# Trig_to_Gate_Converter_ctrl_V1.net
KiCad netlist of a schematic drawn in EAGLE
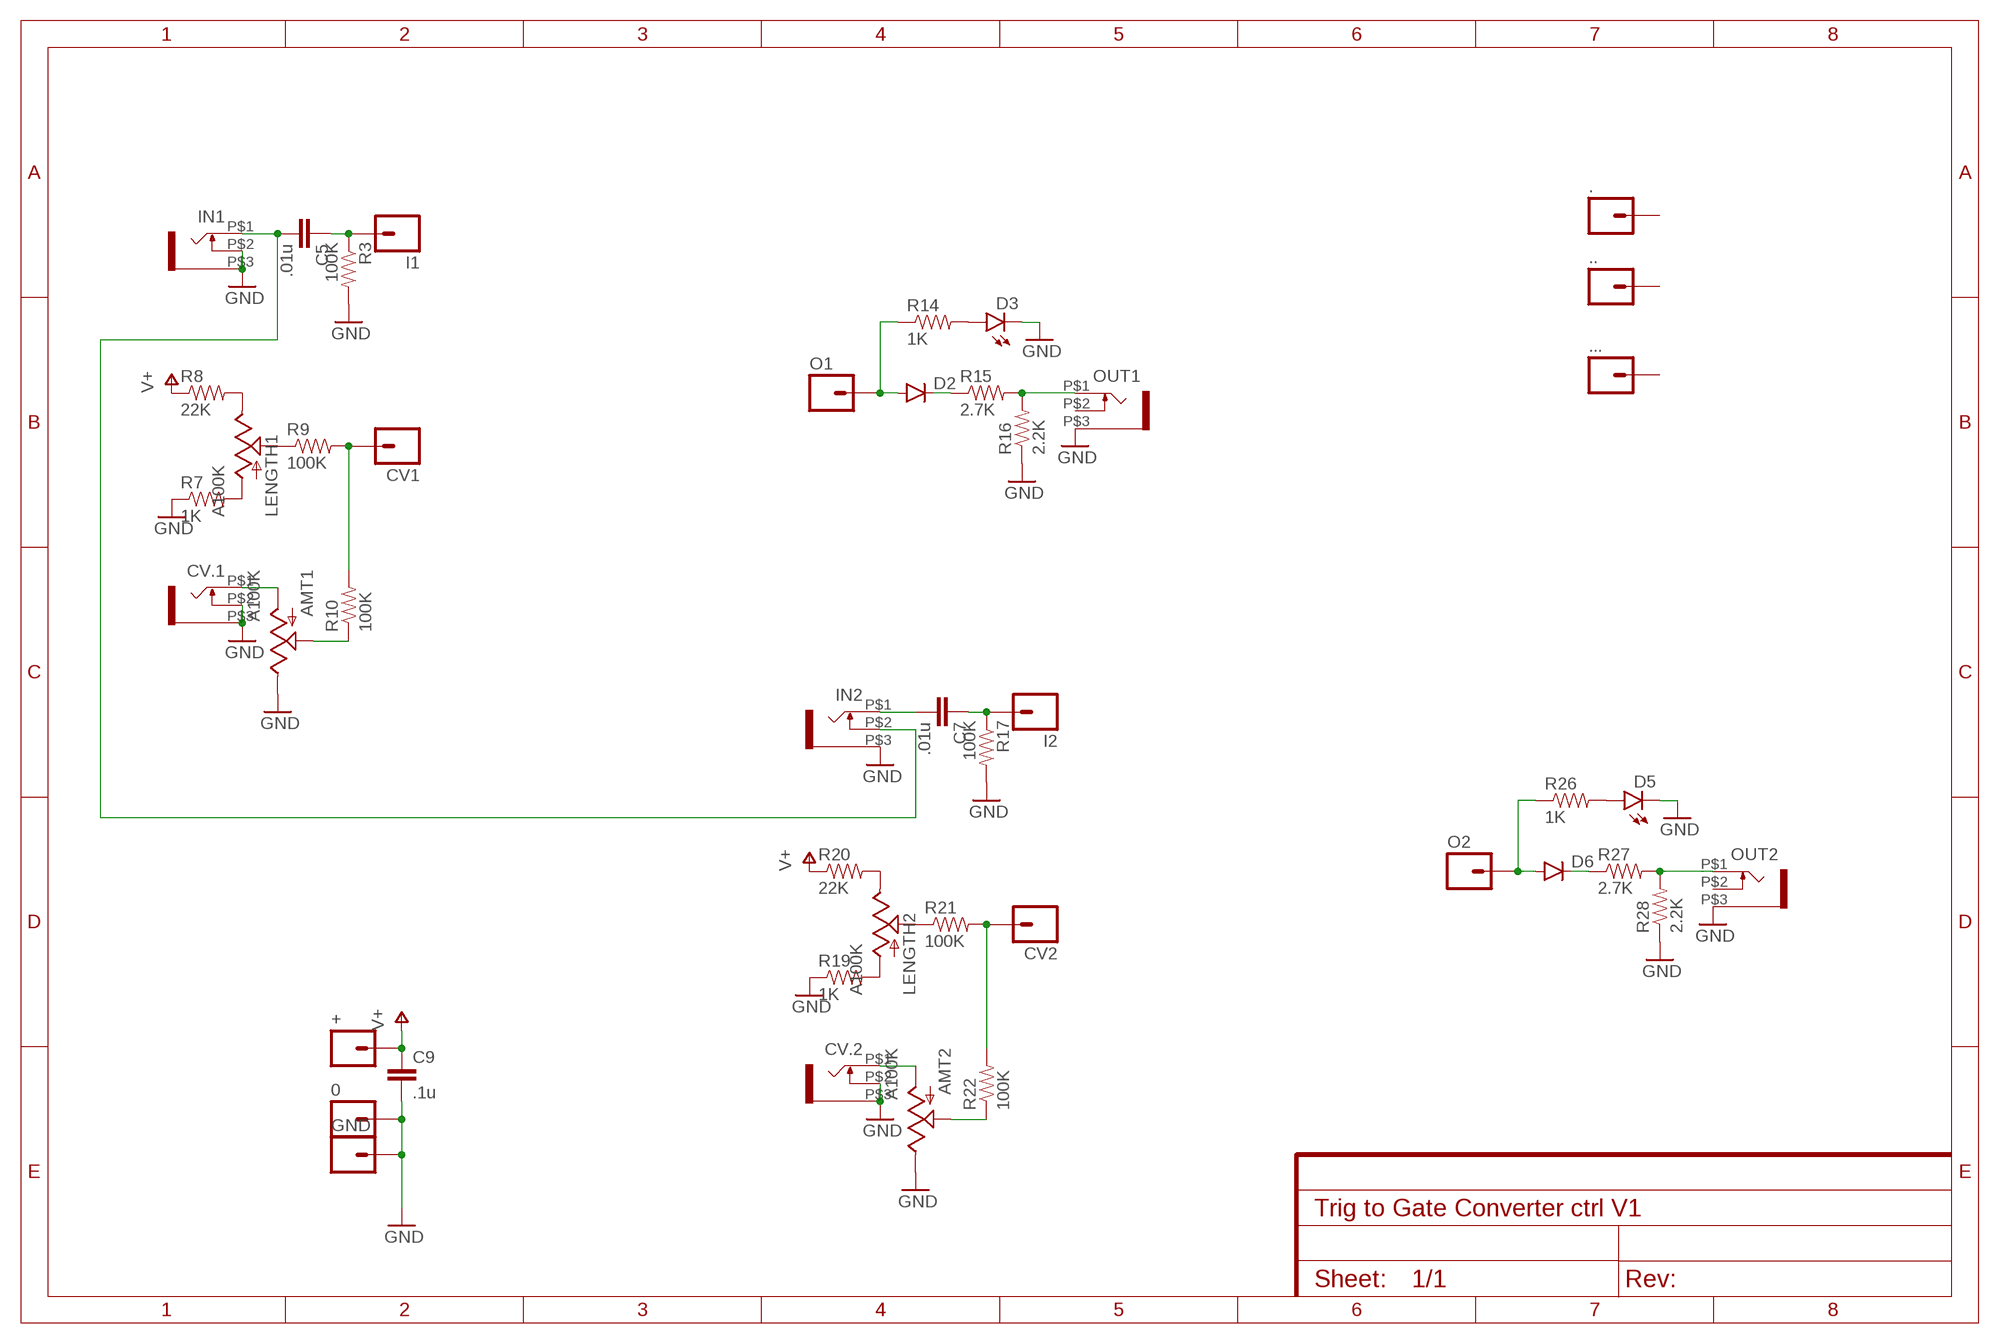
[diagram p0: schematic, sheet 1]

(export (version "E")
  (design (tool "Eeschema 10.0.6"))
  (components
    (comp (ref "+")
      (value "M01PTH")
      (footprint "eagle-import:1X01")
      (libsource (lib "eagle-import") (part "M01PTH"))
    )
    (comp (ref ".")
      (value "M01PTH")
      (footprint "eagle-import:1X01")
      (libsource (lib "eagle-import") (part "M01PTH"))
    )
    (comp (ref "..")
      (value "M01PTH")
      (footprint "eagle-import:1X01")
      (libsource (lib "eagle-import") (part "M01PTH"))
    )
    (comp (ref "...")
      (value "M01PTH")
      (footprint "eagle-import:1X01")
      (libsource (lib "eagle-import") (part "M01PTH"))
    )
    (comp (ref "0")
      (value "M01PTH")
      (footprint "eagle-import:1X01")
      (libsource (lib "eagle-import") (part "M01PTH"))
    )
    (comp (ref "AMT1")
      (value "A100K")
      (footprint "eagle-import:ALPS_POT")
      (libsource (lib "eagle-import") (part "POT"))
    )
    (comp (ref "AMT2")
      (value "A100K")
      (footprint "eagle-import:ALPS_POT")
      (libsource (lib "eagle-import") (part "POT"))
    )
    (comp (ref "C5")
      (value ".01u")
      (footprint "eagle-import:0805")
      (libsource (lib "eagle-import") (part "CAP0805"))
    )
    (comp (ref "C7")
      (value ".01u")
      (footprint "eagle-import:0805")
      (libsource (lib "eagle-import") (part "CAP0805"))
    )
    (comp (ref "C9")
      (value ".1u")
      (footprint "eagle-import:0805")
      (libsource (lib "eagle-import") (part "CAP0805"))
    )
    (comp (ref "CV.1")
      (value "WQP-PJ301M-12_JACK")
      (footprint "eagle-import:WQP-PJ301M-12_JACK")
      (libsource (lib "eagle-import") (part "WQP-PJ301M-12_JACK"))
    )
    (comp (ref "CV.2")
      (value "WQP-PJ301M-12_JACK")
      (footprint "eagle-import:WQP-PJ301M-12_JACK")
      (libsource (lib "eagle-import") (part "WQP-PJ301M-12_JACK"))
    )
    (comp (ref "CV1")
      (value "M01PTH")
      (footprint "eagle-import:1X01")
      (libsource (lib "eagle-import") (part "M01PTH"))
    )
    (comp (ref "CV2")
      (value "M01PTH")
      (footprint "eagle-import:1X01")
      (libsource (lib "eagle-import") (part "M01PTH"))
    )
    (comp (ref "D2")
      (value "DIODESOD123")
      (footprint "eagle-import:SOD-123")
      (libsource (lib "eagle-import") (part "DIODESOD123"))
    )
    (comp (ref "D3")
      (value "LED3MM")
      (footprint "eagle-import:LED3MM")
      (libsource (lib "eagle-import") (part "LED3MM"))
    )
    (comp (ref "D5")
      (value "LED3MM")
      (footprint "eagle-import:LED3MM")
      (libsource (lib "eagle-import") (part "LED3MM"))
    )
    (comp (ref "D6")
      (value "DIODESOD123")
      (footprint "eagle-import:SOD-123")
      (libsource (lib "eagle-import") (part "DIODESOD123"))
    )
    (comp (ref "GND")
      (value "M01PTH")
      (footprint "eagle-import:1X01")
      (libsource (lib "eagle-import") (part "M01PTH"))
    )
    (comp (ref "I1")
      (value "M01PTH")
      (footprint "eagle-import:1X01")
      (libsource (lib "eagle-import") (part "M01PTH"))
    )
    (comp (ref "I2")
      (value "M01PTH")
      (footprint "eagle-import:1X01")
      (libsource (lib "eagle-import") (part "M01PTH"))
    )
    (comp (ref "IN1")
      (value "WQP-PJ301M-12_JACK")
      (footprint "eagle-import:WQP-PJ301M-12_JACK")
      (libsource (lib "eagle-import") (part "WQP-PJ301M-12_JACK"))
    )
    (comp (ref "IN2")
      (value "WQP-PJ301M-12_JACK")
      (footprint "eagle-import:WQP-PJ301M-12_JACK")
      (libsource (lib "eagle-import") (part "WQP-PJ301M-12_JACK"))
    )
    (comp (ref "LENGTH1")
      (value "A100K")
      (footprint "eagle-import:ALPS_POT")
      (libsource (lib "eagle-import") (part "POT"))
    )
    (comp (ref "LENGTH2")
      (value "A100K")
      (footprint "eagle-import:ALPS_POT")
      (libsource (lib "eagle-import") (part "POT"))
    )
    (comp (ref "O1")
      (value "M01PTH")
      (footprint "eagle-import:1X01")
      (libsource (lib "eagle-import") (part "M01PTH"))
    )
    (comp (ref "O2")
      (value "M01PTH")
      (footprint "eagle-import:1X01")
      (libsource (lib "eagle-import") (part "M01PTH"))
    )
    (comp (ref "OUT1")
      (value "WQP-PJ301M-12_JACK")
      (footprint "eagle-import:WQP-PJ301M-12_JACK")
      (libsource (lib "eagle-import") (part "WQP-PJ301M-12_JACK"))
    )
    (comp (ref "OUT2")
      (value "WQP-PJ301M-12_JACK")
      (footprint "eagle-import:WQP-PJ301M-12_JACK")
      (libsource (lib "eagle-import") (part "WQP-PJ301M-12_JACK"))
    )
    (comp (ref "R3")
      (value "100K")
      (footprint "eagle-import:0805")
      (libsource (lib "eagle-import") (part "RESISTOR0805-RES"))
    )
    (comp (ref "R7")
      (value "1K")
      (footprint "eagle-import:0805")
      (libsource (lib "eagle-import") (part "RESISTOR0805-RES"))
    )
    (comp (ref "R8")
      (value "22K")
      (footprint "eagle-import:0805")
      (libsource (lib "eagle-import") (part "RESISTOR0805-RES"))
    )
    (comp (ref "R9")
      (value "100K")
      (footprint "eagle-import:0805")
      (libsource (lib "eagle-import") (part "RESISTOR0805-RES"))
    )
    (comp (ref "R10")
      (value "100K")
      (footprint "eagle-import:0805")
      (libsource (lib "eagle-import") (part "RESISTOR0805-RES"))
    )
    (comp (ref "R14")
      (value "1K")
      (footprint "eagle-import:0805")
      (libsource (lib "eagle-import") (part "RESISTOR0805-RES"))
    )
    (comp (ref "R15")
      (value "2.7K")
      (footprint "eagle-import:0805")
      (libsource (lib "eagle-import") (part "RESISTOR0805-RES"))
    )
    (comp (ref "R16")
      (value "2.2K")
      (footprint "eagle-import:0805")
      (libsource (lib "eagle-import") (part "RESISTOR0805-RES"))
    )
    (comp (ref "R17")
      (value "100K")
      (footprint "eagle-import:0805")
      (libsource (lib "eagle-import") (part "RESISTOR0805-RES"))
    )
    (comp (ref "R19")
      (value "1K")
      (footprint "eagle-import:0805")
      (libsource (lib "eagle-import") (part "RESISTOR0805-RES"))
    )
    (comp (ref "R20")
      (value "22K")
      (footprint "eagle-import:0805")
      (libsource (lib "eagle-import") (part "RESISTOR0805-RES"))
    )
    (comp (ref "R21")
      (value "100K")
      (footprint "eagle-import:0805")
      (libsource (lib "eagle-import") (part "RESISTOR0805-RES"))
    )
    (comp (ref "R22")
      (value "100K")
      (footprint "eagle-import:0805")
      (libsource (lib "eagle-import") (part "RESISTOR0805-RES"))
    )
    (comp (ref "R26")
      (value "1K")
      (footprint "eagle-import:0805")
      (libsource (lib "eagle-import") (part "RESISTOR0805-RES"))
    )
    (comp (ref "R27")
      (value "2.7K")
      (footprint "eagle-import:0805")
      (libsource (lib "eagle-import") (part "RESISTOR0805-RES"))
    )
    (comp (ref "R28")
      (value "2.2K")
      (footprint "eagle-import:0805")
      (libsource (lib "eagle-import") (part "RESISTOR0805-RES"))
    )
  )
  (nets
    (net (code "1") (name "GND") (class "Default")
      (node (ref "0") (pin "1") (pinfunction "1_1") (pintype "passive"))
      (node (ref "AMT1") (pin "P$1") (pinfunction "E_P$1") (pintype "passive"))
      (node (ref "AMT2") (pin "P$1") (pinfunction "E_P$1") (pintype "passive"))
      (node (ref "C9") (pin "2") (pinfunction "2_2") (pintype "passive"))
      (node (ref "CV.1") (pin "P$2") (pinfunction "3_P$2") (pintype "passive"))
      (node (ref "CV.1") (pin "P$3") (pinfunction "1_P$3") (pintype "passive"))
      (node (ref "CV.2") (pin "P$2") (pinfunction "3_P$2") (pintype "passive"))
      (node (ref "CV.2") (pin "P$3") (pinfunction "1_P$3") (pintype "passive"))
      (node (ref "D3") (pin "K") (pinfunction "C_K") (pintype "passive"))
      (node (ref "D5") (pin "K") (pinfunction "C_K") (pintype "passive"))
      (node (ref "GND") (pin "1") (pinfunction "1_1") (pintype "passive"))
      (node (ref "IN1") (pin "P$2") (pinfunction "3_P$2") (pintype "passive"))
      (node (ref "IN1") (pin "P$3") (pinfunction "1_P$3") (pintype "passive"))
      (node (ref "IN2") (pin "P$3") (pinfunction "1_P$3") (pintype "passive"))
      (node (ref "OUT1") (pin "P$3") (pinfunction "1_P$3") (pintype "passive"))
      (node (ref "OUT2") (pin "P$3") (pinfunction "1_P$3") (pintype "passive"))
      (node (ref "R16") (pin "1") (pinfunction "1_1") (pintype "passive"))
      (node (ref "R17") (pin "2") (pinfunction "2_2") (pintype "passive"))
      (node (ref "R19") (pin "1") (pinfunction "1_1") (pintype "passive"))
      (node (ref "R28") (pin "1") (pinfunction "1_1") (pintype "passive"))
      (node (ref "R3") (pin "2") (pinfunction "2_2") (pintype "passive"))
      (node (ref "R7") (pin "1") (pinfunction "1_1") (pintype "passive"))
    )
    (net (code "2") (name "Net-(AMT1-A)") (class "Default")
      (node (ref "AMT1") (pin "P$3") (pinfunction "A_P$3") (pintype "passive"))
      (node (ref "CV.1") (pin "P$1") (pinfunction "2_P$1") (pintype "passive"))
    )
    (net (code "3") (name "Net-(AMT1-S)") (class "Default")
      (node (ref "AMT1") (pin "P$2") (pinfunction "S_P$2") (pintype "passive"))
      (node (ref "R10") (pin "1") (pinfunction "1_1") (pintype "passive"))
    )
    (net (code "4") (name "Net-(AMT2-A)") (class "Default")
      (node (ref "AMT2") (pin "P$3") (pinfunction "A_P$3") (pintype "passive"))
      (node (ref "CV.2") (pin "P$1") (pinfunction "2_P$1") (pintype "passive"))
    )
    (net (code "5") (name "Net-(AMT2-S)") (class "Default")
      (node (ref "AMT2") (pin "P$2") (pinfunction "S_P$2") (pintype "passive"))
      (node (ref "R22") (pin "1") (pinfunction "1_1") (pintype "passive"))
    )
    (net (code "6") (name "Net-(C5-Pad1)") (class "Default")
      (node (ref "C5") (pin "1") (pinfunction "1_1") (pintype "passive"))
      (node (ref "I1") (pin "1") (pinfunction "1_1") (pintype "passive"))
      (node (ref "R3") (pin "1") (pinfunction "1_1") (pintype "passive"))
    )
    (net (code "7") (name "Net-(C7-Pad1)") (class "Default")
      (node (ref "C7") (pin "1") (pinfunction "1_1") (pintype "passive"))
      (node (ref "I2") (pin "1") (pinfunction "1_1") (pintype "passive"))
      (node (ref "R17") (pin "1") (pinfunction "1_1") (pintype "passive"))
    )
    (net (code "8") (name "Net-(CV1-Pad1)") (class "Default")
      (node (ref "CV1") (pin "1") (pinfunction "1_1") (pintype "passive"))
      (node (ref "R10") (pin "2") (pinfunction "2_2") (pintype "passive"))
      (node (ref "R9") (pin "2") (pinfunction "2_2") (pintype "passive"))
    )
    (net (code "9") (name "Net-(CV2-Pad1)") (class "Default")
      (node (ref "CV2") (pin "1") (pinfunction "1_1") (pintype "passive"))
      (node (ref "R21") (pin "2") (pinfunction "2_2") (pintype "passive"))
      (node (ref "R22") (pin "2") (pinfunction "2_2") (pintype "passive"))
    )
    (net (code "10") (name "Net-(D2-PadA)") (class "Default")
      (node (ref "D2") (pin "A") (pinfunction "A_A") (pintype "passive"))
      (node (ref "O1") (pin "1") (pinfunction "1_1") (pintype "passive"))
      (node (ref "R14") (pin "1") (pinfunction "1_1") (pintype "passive"))
    )
    (net (code "11") (name "Net-(D2-PadC)") (class "Default")
      (node (ref "D2") (pin "C") (pinfunction "C_C") (pintype "passive"))
      (node (ref "R15") (pin "1") (pinfunction "1_1") (pintype "passive"))
    )
    (net (code "12") (name "Net-(D3-PadA)") (class "Default")
      (node (ref "D3") (pin "A") (pinfunction "A_A") (pintype "passive"))
      (node (ref "R14") (pin "2") (pinfunction "2_2") (pintype "passive"))
    )
    (net (code "13") (name "Net-(D5-PadA)") (class "Default")
      (node (ref "D5") (pin "A") (pinfunction "A_A") (pintype "passive"))
      (node (ref "R26") (pin "2") (pinfunction "2_2") (pintype "passive"))
    )
    (net (code "14") (name "Net-(D6-PadA)") (class "Default")
      (node (ref "D6") (pin "A") (pinfunction "A_A") (pintype "passive"))
      (node (ref "O2") (pin "1") (pinfunction "1_1") (pintype "passive"))
      (node (ref "R26") (pin "1") (pinfunction "1_1") (pintype "passive"))
    )
    (net (code "15") (name "Net-(D6-PadC)") (class "Default")
      (node (ref "D6") (pin "C") (pinfunction "C_C") (pintype "passive"))
      (node (ref "R27") (pin "1") (pinfunction "1_1") (pintype "passive"))
    )
    (net (code "16") (name "Net-(IN1-2)") (class "Default")
      (node (ref "C5") (pin "2") (pinfunction "2_2") (pintype "passive"))
      (node (ref "IN1") (pin "P$1") (pinfunction "2_P$1") (pintype "passive"))
      (node (ref "IN2") (pin "P$2") (pinfunction "3_P$2") (pintype "passive"))
    )
    (net (code "17") (name "Net-(IN2-2)") (class "Default")
      (node (ref "C7") (pin "2") (pinfunction "2_2") (pintype "passive"))
      (node (ref "IN2") (pin "P$1") (pinfunction "2_P$1") (pintype "passive"))
    )
    (net (code "18") (name "Net-(LENGTH1-A)") (class "Default")
      (node (ref "LENGTH1") (pin "P$3") (pinfunction "A_P$3") (pintype "passive"))
      (node (ref "R7") (pin "2") (pinfunction "2_2") (pintype "passive"))
    )
    (net (code "19") (name "Net-(LENGTH1-E)") (class "Default")
      (node (ref "LENGTH1") (pin "P$1") (pinfunction "E_P$1") (pintype "passive"))
      (node (ref "R8") (pin "2") (pinfunction "2_2") (pintype "passive"))
    )
    (net (code "20") (name "Net-(LENGTH1-S)") (class "Default")
      (node (ref "LENGTH1") (pin "P$2") (pinfunction "S_P$2") (pintype "passive"))
      (node (ref "R9") (pin "1") (pinfunction "1_1") (pintype "passive"))
    )
    (net (code "21") (name "Net-(LENGTH2-A)") (class "Default")
      (node (ref "LENGTH2") (pin "P$3") (pinfunction "A_P$3") (pintype "passive"))
      (node (ref "R19") (pin "2") (pinfunction "2_2") (pintype "passive"))
    )
    (net (code "22") (name "Net-(LENGTH2-E)") (class "Default")
      (node (ref "LENGTH2") (pin "P$1") (pinfunction "E_P$1") (pintype "passive"))
      (node (ref "R20") (pin "2") (pinfunction "2_2") (pintype "passive"))
    )
    (net (code "23") (name "Net-(LENGTH2-S)") (class "Default")
      (node (ref "LENGTH2") (pin "P$2") (pinfunction "S_P$2") (pintype "passive"))
      (node (ref "R21") (pin "1") (pinfunction "1_1") (pintype "passive"))
    )
    (net (code "24") (name "Net-(OUT1-2)") (class "Default")
      (node (ref "OUT1") (pin "P$1") (pinfunction "2_P$1") (pintype "passive"))
      (node (ref "R15") (pin "2") (pinfunction "2_2") (pintype "passive"))
      (node (ref "R16") (pin "2") (pinfunction "2_2") (pintype "passive"))
    )
    (net (code "25") (name "Net-(OUT2-2)") (class "Default")
      (node (ref "OUT2") (pin "P$1") (pinfunction "2_P$1") (pintype "passive"))
      (node (ref "R27") (pin "2") (pinfunction "2_2") (pintype "passive"))
      (node (ref "R28") (pin "2") (pinfunction "2_2") (pintype "passive"))
    )
    (net (code "26") (name "V+") (class "Default")
      (node (ref "+") (pin "1") (pinfunction "1_1") (pintype "passive"))
      (node (ref "C9") (pin "1") (pinfunction "1_1") (pintype "passive"))
      (node (ref "R20") (pin "1") (pinfunction "1_1") (pintype "passive"))
      (node (ref "R8") (pin "1") (pinfunction "1_1") (pintype "passive"))
    )
    (net (code "27") (name "unconnected-(.-Pad1)") (class "Default")
      (node (ref ".") (pin "1") (pinfunction "1_1") (pintype "passive"))
    )
    (net (code "28") (name "unconnected-(..-Pad1)") (class "Default")
      (node (ref "..") (pin "1") (pinfunction "1_1") (pintype "passive"))
    )
    (net (code "29") (name "unconnected-(...-Pad1)") (class "Default")
      (node (ref "...") (pin "1") (pinfunction "1_1") (pintype "passive"))
    )
    (net (code "30") (name "unconnected-(OUT1-3-PadP$2)") (class "Default")
      (node (ref "OUT1") (pin "P$2") (pinfunction "3_P$2") (pintype "passive"))
    )
    (net (code "31") (name "unconnected-(OUT2-3-PadP$2)") (class "Default")
      (node (ref "OUT2") (pin "P$2") (pinfunction "3_P$2") (pintype "passive"))
    )
  )
)
